# 2_waffling60-DB_matrix.net
KiCad netlist of a schematic drawn in Altium Designer
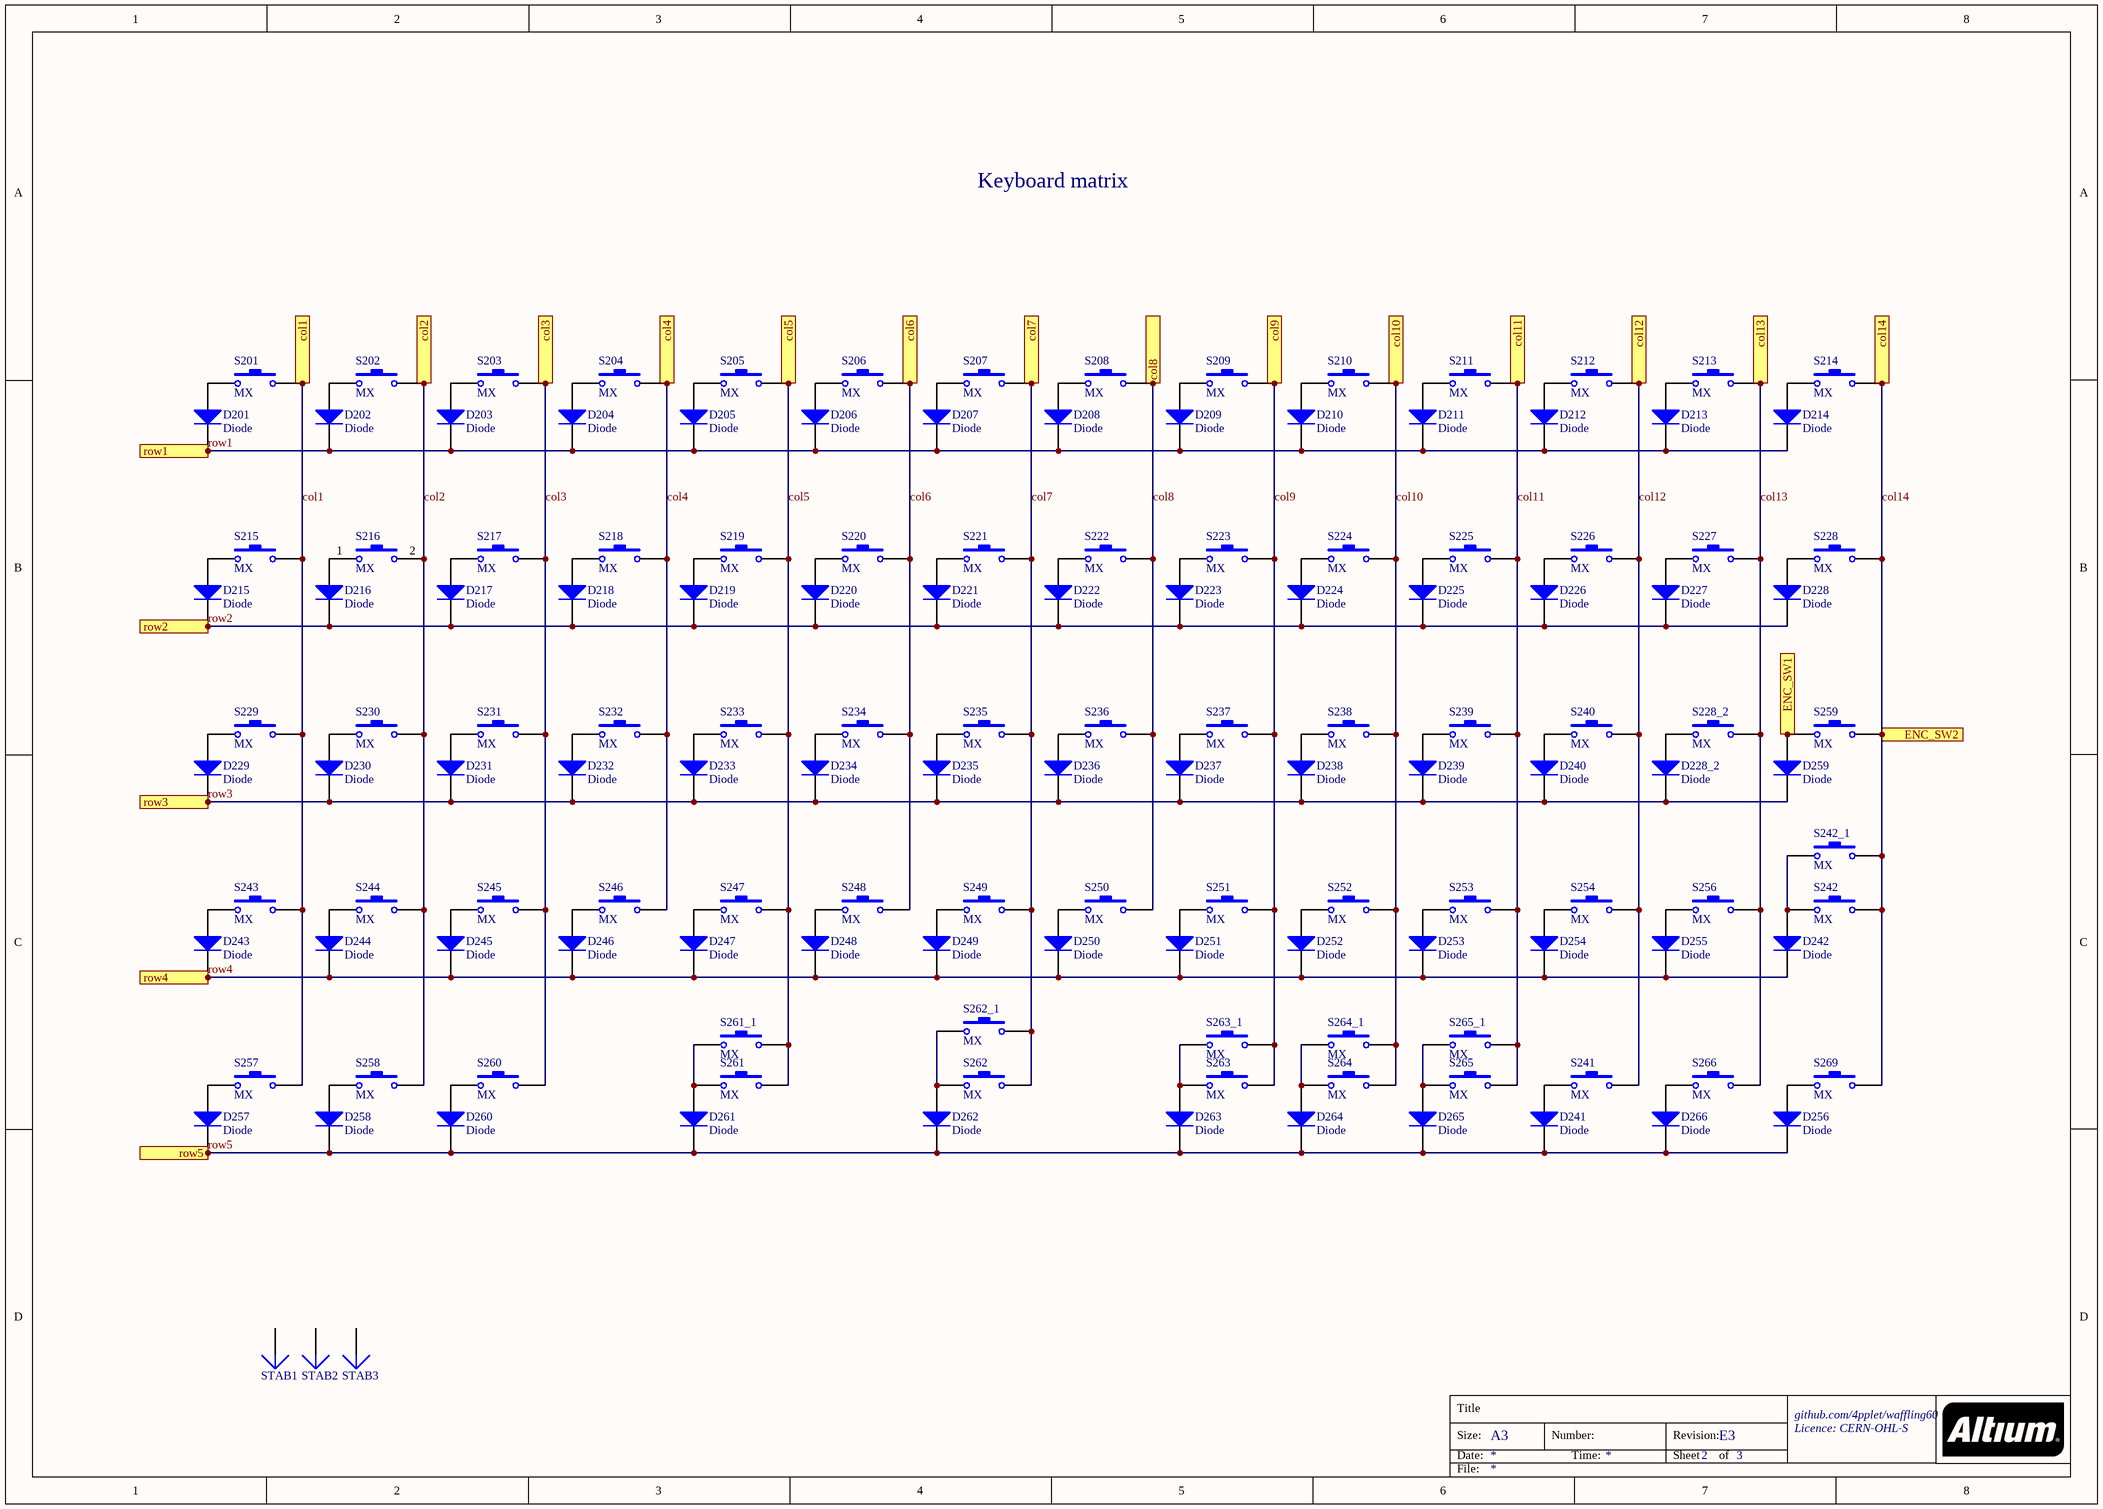
[diagram p0: 2_waffling60-DB_matrix.SchDoc]

(export (version "E")
  (design (tool "Eeschema 10.0.6"))
  (components
    (comp (ref "D201")
      (value "Diode")
      (footprint "SOD-123")
      (description "Default Diode")
      (fields (field (name "LCSC PART #") "C81598") (field (name "MRF.PART") "1N4148W"))
      (libsource (lib "Miscellaneous Devices") (part "Diode"))
    )
    (comp (ref "D202")
      (value "Diode")
      (footprint "SOD-123")
      (description "Default Diode")
      (fields (field (name "LCSC PART #") "C81598") (field (name "MRF.PART") "1N4148W"))
      (libsource (lib "Miscellaneous Devices") (part "Diode"))
    )
    (comp (ref "D203")
      (value "Diode")
      (footprint "SOD-123")
      (description "Default Diode")
      (fields (field (name "LCSC PART #") "C81598") (field (name "MRF.PART") "1N4148W"))
      (libsource (lib "Miscellaneous Devices") (part "Diode"))
    )
    (comp (ref "D204")
      (value "Diode")
      (footprint "SOD-123")
      (description "Default Diode")
      (fields (field (name "LCSC PART #") "C81598") (field (name "MRF.PART") "1N4148W"))
      (libsource (lib "Miscellaneous Devices") (part "Diode"))
    )
    (comp (ref "D205")
      (value "Diode")
      (footprint "SOD-123")
      (description "Default Diode")
      (fields (field (name "LCSC PART #") "C81598") (field (name "MRF.PART") "1N4148W"))
      (libsource (lib "Miscellaneous Devices") (part "Diode"))
    )
    (comp (ref "D206")
      (value "Diode")
      (footprint "SOD-123")
      (description "Default Diode")
      (fields (field (name "LCSC PART #") "C81598") (field (name "MRF.PART") "1N4148W"))
      (libsource (lib "Miscellaneous Devices") (part "Diode"))
    )
    (comp (ref "D207")
      (value "Diode")
      (footprint "SOD-123")
      (description "Default Diode")
      (fields (field (name "LCSC PART #") "C81598") (field (name "MRF.PART") "1N4148W"))
      (libsource (lib "Miscellaneous Devices") (part "Diode"))
    )
    (comp (ref "D208")
      (value "Diode")
      (footprint "SOD-123")
      (description "Default Diode")
      (fields (field (name "LCSC PART #") "C81598") (field (name "MRF.PART") "1N4148W"))
      (libsource (lib "Miscellaneous Devices") (part "Diode"))
    )
    (comp (ref "D209")
      (value "Diode")
      (footprint "SOD-123")
      (description "Default Diode")
      (fields (field (name "LCSC PART #") "C81598") (field (name "MRF.PART") "1N4148W"))
      (libsource (lib "Miscellaneous Devices") (part "Diode"))
    )
    (comp (ref "D210")
      (value "Diode")
      (footprint "SOD-123")
      (description "Default Diode")
      (fields (field (name "LCSC PART #") "C81598") (field (name "MRF.PART") "1N4148W"))
      (libsource (lib "Miscellaneous Devices") (part "Diode"))
    )
    (comp (ref "D211")
      (value "Diode")
      (footprint "SOD-123")
      (description "Default Diode")
      (fields (field (name "LCSC PART #") "C81598") (field (name "MRF.PART") "1N4148W"))
      (libsource (lib "Miscellaneous Devices") (part "Diode"))
    )
    (comp (ref "D212")
      (value "Diode")
      (footprint "SOD-123")
      (description "Default Diode")
      (fields (field (name "LCSC PART #") "C81598") (field (name "MRF.PART") "1N4148W"))
      (libsource (lib "Miscellaneous Devices") (part "Diode"))
    )
    (comp (ref "D213")
      (value "Diode")
      (footprint "SOD-123")
      (description "Default Diode")
      (fields (field (name "LCSC PART #") "C81598") (field (name "MRF.PART") "1N4148W"))
      (libsource (lib "Miscellaneous Devices") (part "Diode"))
    )
    (comp (ref "D214")
      (value "Diode")
      (footprint "SOD-123")
      (description "Default Diode")
      (fields (field (name "LCSC PART #") "C81598") (field (name "MRF.PART") "1N4148W"))
      (libsource (lib "Miscellaneous Devices") (part "Diode"))
    )
    (comp (ref "D215")
      (value "Diode")
      (footprint "SOD-123")
      (description "Default Diode")
      (fields (field (name "LCSC PART #") "C81598") (field (name "MRF.PART") "1N4148W"))
      (libsource (lib "Miscellaneous Devices") (part "Diode"))
    )
    (comp (ref "D216")
      (value "Diode")
      (footprint "SOD-123")
      (description "Default Diode")
      (fields (field (name "LCSC PART #") "C81598") (field (name "MRF.PART") "1N4148W"))
      (libsource (lib "Miscellaneous Devices") (part "Diode"))
    )
    (comp (ref "D217")
      (value "Diode")
      (footprint "SOD-123")
      (description "Default Diode")
      (fields (field (name "LCSC PART #") "C81598") (field (name "MRF.PART") "1N4148W"))
      (libsource (lib "Miscellaneous Devices") (part "Diode"))
    )
    (comp (ref "D218")
      (value "Diode")
      (footprint "SOD-123")
      (description "Default Diode")
      (fields (field (name "LCSC PART #") "C81598") (field (name "MRF.PART") "1N4148W"))
      (libsource (lib "Miscellaneous Devices") (part "Diode"))
    )
    (comp (ref "D219")
      (value "Diode")
      (footprint "SOD-123")
      (description "Default Diode")
      (fields (field (name "LCSC PART #") "C81598") (field (name "MRF.PART") "1N4148W"))
      (libsource (lib "Miscellaneous Devices") (part "Diode"))
    )
    (comp (ref "D220")
      (value "Diode")
      (footprint "SOD-123")
      (description "Default Diode")
      (fields (field (name "LCSC PART #") "C81598") (field (name "MRF.PART") "1N4148W"))
      (libsource (lib "Miscellaneous Devices") (part "Diode"))
    )
    (comp (ref "D221")
      (value "Diode")
      (footprint "SOD-123")
      (description "Default Diode")
      (fields (field (name "LCSC PART #") "C81598") (field (name "MRF.PART") "1N4148W"))
      (libsource (lib "Miscellaneous Devices") (part "Diode"))
    )
    (comp (ref "D222")
      (value "Diode")
      (footprint "SOD-123")
      (description "Default Diode")
      (fields (field (name "LCSC PART #") "C81598") (field (name "MRF.PART") "1N4148W"))
      (libsource (lib "Miscellaneous Devices") (part "Diode"))
    )
    (comp (ref "D223")
      (value "Diode")
      (footprint "SOD-123")
      (description "Default Diode")
      (fields (field (name "LCSC PART #") "C81598") (field (name "MRF.PART") "1N4148W"))
      (libsource (lib "Miscellaneous Devices") (part "Diode"))
    )
    (comp (ref "D224")
      (value "Diode")
      (footprint "SOD-123")
      (description "Default Diode")
      (fields (field (name "LCSC PART #") "C81598") (field (name "MRF.PART") "1N4148W"))
      (libsource (lib "Miscellaneous Devices") (part "Diode"))
    )
    (comp (ref "D225")
      (value "Diode")
      (footprint "SOD-123")
      (description "Default Diode")
      (fields (field (name "LCSC PART #") "C81598") (field (name "MRF.PART") "1N4148W"))
      (libsource (lib "Miscellaneous Devices") (part "Diode"))
    )
    (comp (ref "D226")
      (value "Diode")
      (footprint "SOD-123")
      (description "Default Diode")
      (fields (field (name "LCSC PART #") "C81598") (field (name "MRF.PART") "1N4148W"))
      (libsource (lib "Miscellaneous Devices") (part "Diode"))
    )
    (comp (ref "D227")
      (value "Diode")
      (footprint "SOD-123")
      (description "Default Diode")
      (fields (field (name "LCSC PART #") "C81598") (field (name "MRF.PART") "1N4148W"))
      (libsource (lib "Miscellaneous Devices") (part "Diode"))
    )
    (comp (ref "D228")
      (value "Diode")
      (footprint "SOD-123")
      (description "Default Diode")
      (fields (field (name "LCSC PART #") "C81598") (field (name "MRF.PART") "1N4148W"))
      (libsource (lib "Miscellaneous Devices") (part "Diode"))
    )
    (comp (ref "D228_2")
      (value "Diode")
      (footprint "SOD-123")
      (description "Default Diode")
      (fields (field (name "LCSC PART #") "C81598") (field (name "MRF.PART") "1N4148W"))
      (libsource (lib "Miscellaneous Devices") (part "Diode"))
    )
    (comp (ref "D229")
      (value "Diode")
      (footprint "SOD-123")
      (description "Default Diode")
      (fields (field (name "LCSC PART #") "C81598") (field (name "MRF.PART") "1N4148W"))
      (libsource (lib "Miscellaneous Devices") (part "Diode"))
    )
    (comp (ref "D230")
      (value "Diode")
      (footprint "SOD-123")
      (description "Default Diode")
      (fields (field (name "LCSC PART #") "C81598") (field (name "MRF.PART") "1N4148W"))
      (libsource (lib "Miscellaneous Devices") (part "Diode"))
    )
    (comp (ref "D231")
      (value "Diode")
      (footprint "SOD-123")
      (description "Default Diode")
      (fields (field (name "LCSC PART #") "C81598") (field (name "MRF.PART") "1N4148W"))
      (libsource (lib "Miscellaneous Devices") (part "Diode"))
    )
    (comp (ref "D232")
      (value "Diode")
      (footprint "SOD-123")
      (description "Default Diode")
      (fields (field (name "LCSC PART #") "C81598") (field (name "MRF.PART") "1N4148W"))
      (libsource (lib "Miscellaneous Devices") (part "Diode"))
    )
    (comp (ref "D233")
      (value "Diode")
      (footprint "SOD-123")
      (description "Default Diode")
      (fields (field (name "LCSC PART #") "C81598") (field (name "MRF.PART") "1N4148W"))
      (libsource (lib "Miscellaneous Devices") (part "Diode"))
    )
    (comp (ref "D234")
      (value "Diode")
      (footprint "SOD-123")
      (description "Default Diode")
      (fields (field (name "LCSC PART #") "C81598") (field (name "MRF.PART") "1N4148W"))
      (libsource (lib "Miscellaneous Devices") (part "Diode"))
    )
    (comp (ref "D235")
      (value "Diode")
      (footprint "SOD-123")
      (description "Default Diode")
      (fields (field (name "LCSC PART #") "C81598") (field (name "MRF.PART") "1N4148W"))
      (libsource (lib "Miscellaneous Devices") (part "Diode"))
    )
    (comp (ref "D236")
      (value "Diode")
      (footprint "SOD-123")
      (description "Default Diode")
      (fields (field (name "LCSC PART #") "C81598") (field (name "MRF.PART") "1N4148W"))
      (libsource (lib "Miscellaneous Devices") (part "Diode"))
    )
    (comp (ref "D237")
      (value "Diode")
      (footprint "SOD-123")
      (description "Default Diode")
      (fields (field (name "LCSC PART #") "C81598") (field (name "MRF.PART") "1N4148W"))
      (libsource (lib "Miscellaneous Devices") (part "Diode"))
    )
    (comp (ref "D238")
      (value "Diode")
      (footprint "SOD-123")
      (description "Default Diode")
      (fields (field (name "LCSC PART #") "C81598") (field (name "MRF.PART") "1N4148W"))
      (libsource (lib "Miscellaneous Devices") (part "Diode"))
    )
    (comp (ref "D239")
      (value "Diode")
      (footprint "SOD-123")
      (description "Default Diode")
      (fields (field (name "LCSC PART #") "C81598") (field (name "MRF.PART") "1N4148W"))
      (libsource (lib "Miscellaneous Devices") (part "Diode"))
    )
    (comp (ref "D240")
      (value "Diode")
      (footprint "SOD-123")
      (description "Default Diode")
      (fields (field (name "LCSC PART #") "C81598") (field (name "MRF.PART") "1N4148W"))
      (libsource (lib "Miscellaneous Devices") (part "Diode"))
    )
    (comp (ref "D241")
      (value "Diode")
      (footprint "SOD-123")
      (description "Default Diode")
      (fields (field (name "LCSC PART #") "C81598") (field (name "MRF.PART") "1N4148W"))
      (libsource (lib "Miscellaneous Devices") (part "Diode"))
    )
    (comp (ref "D242")
      (value "Diode")
      (footprint "SOD-123")
      (description "Default Diode")
      (fields (field (name "LCSC PART #") "C81598") (field (name "MRF.PART") "1N4148W"))
      (libsource (lib "Miscellaneous Devices") (part "Diode"))
    )
    (comp (ref "D243")
      (value "Diode")
      (footprint "SOD-123")
      (description "Default Diode")
      (fields (field (name "LCSC PART #") "C81598") (field (name "MRF.PART") "1N4148W"))
      (libsource (lib "Miscellaneous Devices") (part "Diode"))
    )
    (comp (ref "D244")
      (value "Diode")
      (footprint "SOD-123")
      (description "Default Diode")
      (fields (field (name "LCSC PART #") "C81598") (field (name "MRF.PART") "1N4148W"))
      (libsource (lib "Miscellaneous Devices") (part "Diode"))
    )
    (comp (ref "D245")
      (value "Diode")
      (footprint "SOD-123")
      (description "Default Diode")
      (fields (field (name "LCSC PART #") "C81598") (field (name "MRF.PART") "1N4148W"))
      (libsource (lib "Miscellaneous Devices") (part "Diode"))
    )
    (comp (ref "D246")
      (value "Diode")
      (footprint "SOD-123")
      (description "Default Diode")
      (fields (field (name "LCSC PART #") "C81598") (field (name "MRF.PART") "1N4148W"))
      (libsource (lib "Miscellaneous Devices") (part "Diode"))
    )
    (comp (ref "D247")
      (value "Diode")
      (footprint "SOD-123")
      (description "Default Diode")
      (fields (field (name "LCSC PART #") "C81598") (field (name "MRF.PART") "1N4148W"))
      (libsource (lib "Miscellaneous Devices") (part "Diode"))
    )
    (comp (ref "D248")
      (value "Diode")
      (footprint "SOD-123")
      (description "Default Diode")
      (fields (field (name "LCSC PART #") "C81598") (field (name "MRF.PART") "1N4148W"))
      (libsource (lib "Miscellaneous Devices") (part "Diode"))
    )
    (comp (ref "D249")
      (value "Diode")
      (footprint "SOD-123")
      (description "Default Diode")
      (fields (field (name "LCSC PART #") "C81598") (field (name "MRF.PART") "1N4148W"))
      (libsource (lib "Miscellaneous Devices") (part "Diode"))
    )
    (comp (ref "D250")
      (value "Diode")
      (footprint "SOD-123")
      (description "Default Diode")
      (fields (field (name "LCSC PART #") "C81598") (field (name "MRF.PART") "1N4148W"))
      (libsource (lib "Miscellaneous Devices") (part "Diode"))
    )
    (comp (ref "D251")
      (value "Diode")
      (footprint "SOD-123")
      (description "Default Diode")
      (fields (field (name "LCSC PART #") "C81598") (field (name "MRF.PART") "1N4148W"))
      (libsource (lib "Miscellaneous Devices") (part "Diode"))
    )
    (comp (ref "D252")
      (value "Diode")
      (footprint "SOD-123")
      (description "Default Diode")
      (fields (field (name "LCSC PART #") "C81598") (field (name "MRF.PART") "1N4148W"))
      (libsource (lib "Miscellaneous Devices") (part "Diode"))
    )
    (comp (ref "D253")
      (value "Diode")
      (footprint "SOD-123")
      (description "Default Diode")
      (fields (field (name "LCSC PART #") "C81598") (field (name "MRF.PART") "1N4148W"))
      (libsource (lib "Miscellaneous Devices") (part "Diode"))
    )
    (comp (ref "D254")
      (value "Diode")
      (footprint "SOD-123")
      (description "Default Diode")
      (fields (field (name "LCSC PART #") "C81598") (field (name "MRF.PART") "1N4148W"))
      (libsource (lib "Miscellaneous Devices") (part "Diode"))
    )
    (comp (ref "D255")
      (value "Diode")
      (footprint "SOD-123")
      (description "Default Diode")
      (fields (field (name "LCSC PART #") "C81598") (field (name "MRF.PART") "1N4148W"))
      (libsource (lib "Miscellaneous Devices") (part "Diode"))
    )
    (comp (ref "D256")
      (value "Diode")
      (footprint "SOD-123")
      (description "Default Diode")
      (fields (field (name "LCSC PART #") "C81598") (field (name "MRF.PART") "1N4148W"))
      (libsource (lib "Miscellaneous Devices") (part "Diode"))
    )
    (comp (ref "D257")
      (value "Diode")
      (footprint "SOD-123")
      (description "Default Diode")
      (fields (field (name "LCSC PART #") "C81598") (field (name "MRF.PART") "1N4148W"))
      (libsource (lib "Miscellaneous Devices") (part "Diode"))
    )
    (comp (ref "D258")
      (value "Diode")
      (footprint "SOD-123")
      (description "Default Diode")
      (fields (field (name "LCSC PART #") "C81598") (field (name "MRF.PART") "1N4148W"))
      (libsource (lib "Miscellaneous Devices") (part "Diode"))
    )
    (comp (ref "D259")
      (value "Diode")
      (footprint "SOD-123")
      (description "Default Diode")
      (fields (field (name "LCSC PART #") "C81598") (field (name "MRF.PART") "1N4148W"))
      (libsource (lib "Miscellaneous Devices") (part "Diode"))
    )
    (comp (ref "D260")
      (value "Diode")
      (footprint "SOD-123")
      (description "Default Diode")
      (fields (field (name "LCSC PART #") "C81598") (field (name "MRF.PART") "1N4148W"))
      (libsource (lib "Miscellaneous Devices") (part "Diode"))
    )
    (comp (ref "D261")
      (value "Diode")
      (footprint "SOD-123")
      (description "Default Diode")
      (fields (field (name "LCSC PART #") "C81598") (field (name "MRF.PART") "1N4148W"))
      (libsource (lib "Miscellaneous Devices") (part "Diode"))
    )
    (comp (ref "D262")
      (value "Diode")
      (footprint "SOD-123")
      (description "Default Diode")
      (fields (field (name "LCSC PART #") "C81598") (field (name "MRF.PART") "1N4148W"))
      (libsource (lib "Miscellaneous Devices") (part "Diode"))
    )
    (comp (ref "D263")
      (value "Diode")
      (footprint "SOD-123")
      (description "Default Diode")
      (fields (field (name "LCSC PART #") "C81598") (field (name "MRF.PART") "1N4148W"))
      (libsource (lib "Miscellaneous Devices") (part "Diode"))
    )
    (comp (ref "D264")
      (value "Diode")
      (footprint "SOD-123")
      (description "Default Diode")
      (fields (field (name "LCSC PART #") "C81598") (field (name "MRF.PART") "1N4148W"))
      (libsource (lib "Miscellaneous Devices") (part "Diode"))
    )
    (comp (ref "D265")
      (value "Diode")
      (footprint "SOD-123")
      (description "Default Diode")
      (fields (field (name "LCSC PART #") "C81598") (field (name "MRF.PART") "1N4148W"))
      (libsource (lib "Miscellaneous Devices") (part "Diode"))
    )
    (comp (ref "D266")
      (value "Diode")
      (footprint "SOD-123")
      (description "Default Diode")
      (fields (field (name "LCSC PART #") "C81598") (field (name "MRF.PART") "1N4148W"))
      (libsource (lib "Miscellaneous Devices") (part "Diode"))
    )
    (comp (ref "S201")
      (value "MX")
      (footprint "MX-switch - switched pol")
      (description "Switch")
      (libsource (lib "Miscellaneous Devices") (part "SW-PB"))
    )
    (comp (ref "S202")
      (value "MX")
      (footprint "MX-switch - switched pol")
      (description "Switch")
      (libsource (lib "Miscellaneous Devices") (part "SW-PB"))
    )
    (comp (ref "S203")
      (value "MX")
      (footprint "MX-switch - switched pol")
      (description "Switch")
      (libsource (lib "Miscellaneous Devices") (part "SW-PB"))
    )
    (comp (ref "S204")
      (value "MX")
      (footprint "MX-switch - switched pol")
      (description "Switch")
      (libsource (lib "Miscellaneous Devices") (part "SW-PB"))
    )
    (comp (ref "S205")
      (value "MX")
      (footprint "MX-switch - switched pol")
      (description "Switch")
      (libsource (lib "Miscellaneous Devices") (part "SW-PB"))
    )
    (comp (ref "S206")
      (value "MX")
      (footprint "MX-switch - switched pol")
      (description "Switch")
      (libsource (lib "Miscellaneous Devices") (part "SW-PB"))
    )
    (comp (ref "S207")
      (value "MX")
      (footprint "MX-switch - switched pol")
      (description "Switch")
      (libsource (lib "Miscellaneous Devices") (part "SW-PB"))
    )
    (comp (ref "S208")
      (value "MX")
      (footprint "MX-switch - switched pol")
      (description "Switch")
      (libsource (lib "Miscellaneous Devices") (part "SW-PB"))
    )
    (comp (ref "S209")
      (value "MX")
      (footprint "MX-switch - switched pol")
      (description "Switch")
      (libsource (lib "Miscellaneous Devices") (part "SW-PB"))
    )
    (comp (ref "S210")
      (value "MX")
      (footprint "MX-switch - switched pol")
      (description "Switch")
      (libsource (lib "Miscellaneous Devices") (part "SW-PB"))
    )
    (comp (ref "S211")
      (value "MX")
      (footprint "MX-switch - switched pol")
      (description "Switch")
      (libsource (lib "Miscellaneous Devices") (part "SW-PB"))
    )
    (comp (ref "S212")
      (value "MX")
      (footprint "MX-switch - switched pol")
      (description "Switch")
      (libsource (lib "Miscellaneous Devices") (part "SW-PB"))
    )
    (comp (ref "S213")
      (value "MX")
      (footprint "MX-switch - switched pol")
      (description "Switch")
      (libsource (lib "Miscellaneous Devices") (part "SW-PB"))
    )
    (comp (ref "S214")
      (value "MX")
      (footprint "MX-switch")
      (description "Switch")
      (libsource (lib "Miscellaneous Devices") (part "SW-PB"))
    )
    (comp (ref "S215")
      (value "MX")
      (footprint "MX-switch - switched pol")
      (description "TAB")
      (libsource (lib "Miscellaneous Devices") (part "SW-PB"))
    )
    (comp (ref "S216")
      (value "MX")
      (footprint "MX-switch")
      (description "Switch")
      (libsource (lib "") (part "SW-PB_1"))
    )
    (comp (ref "S217")
      (value "MX")
      (footprint "MX-switch - switched pol")
      (description "Switch")
      (libsource (lib "Miscellaneous Devices") (part "SW-PB"))
    )
    (comp (ref "S218")
      (value "MX")
      (footprint "MX-switch - switched pol")
      (description "Switch")
      (libsource (lib "Miscellaneous Devices") (part "SW-PB"))
    )
    (comp (ref "S219")
      (value "MX")
      (footprint "MX-switch - switched pol")
      (description "Switch")
      (libsource (lib "Miscellaneous Devices") (part "SW-PB"))
    )
    (comp (ref "S220")
      (value "MX")
      (footprint "MX-switch")
      (description "Switch")
      (libsource (lib "Miscellaneous Devices") (part "SW-PB"))
    )
    (comp (ref "S221")
      (value "MX")
      (footprint "MX-switch - switched pol")
      (description "Switch")
      (libsource (lib "Miscellaneous Devices") (part "SW-PB"))
    )
    (comp (ref "S222")
      (value "MX")
      (footprint "MX-switch - switched pol")
      (description "Switch")
      (libsource (lib "Miscellaneous Devices") (part "SW-PB"))
    )
    (comp (ref "S223")
      (value "MX")
      (footprint "MX-switch - switched pol")
      (description "Switch")
      (libsource (lib "Miscellaneous Devices") (part "SW-PB"))
    )
    (comp (ref "S224")
      (value "MX")
      (footprint "MX-switch - switched pol")
      (description "Switch")
      (libsource (lib "Miscellaneous Devices") (part "SW-PB"))
    )
    (comp (ref "S225")
      (value "MX")
      (footprint "MX-switch - switched pol")
      (description "Switch")
      (libsource (lib "Miscellaneous Devices") (part "SW-PB"))
    )
    (comp (ref "S226")
      (value "MX")
      (footprint "MX-switch")
      (description "Switch")
      (libsource (lib "Miscellaneous Devices") (part "SW-PB"))
    )
    (comp (ref "S227")
      (value "MX")
      (footprint "MX-switch")
      (description "Switch")
      (libsource (lib "Miscellaneous Devices") (part "SW-PB"))
    )
    (comp (ref "S228")
      (value "MX")
      (footprint "MX-switch - 1.5U")
      (description "Switch")
      (libsource (lib "Miscellaneous Devices") (part "SW-PB"))
    )
    (comp (ref "S228_2")
      (value "MX")
      (footprint "MX-switch")
      (description "Switch")
      (libsource (lib "Miscellaneous Devices") (part "SW-PB"))
    )
    (comp (ref "S229")
      (value "MX")
      (footprint "MX-switch - CAPS")
      (description "Switch")
      (libsource (lib "Miscellaneous Devices") (part "SW-PB"))
    )
    (comp (ref "S230")
      (value "MX")
      (footprint "MX-switch")
      (description "Switch")
      (libsource (lib "Miscellaneous Devices") (part "SW-PB"))
    )
    (comp (ref "S231")
      (value "MX")
      (footprint "MX-switch - switched pol")
      (description "Switch")
      (libsource (lib "Miscellaneous Devices") (part "SW-PB"))
    )
    (comp (ref "S232")
      (value "MX")
      (footprint "MX-switch - switched pol")
      (description "Switch")
      (libsource (lib "Miscellaneous Devices") (part "SW-PB"))
    )
    (comp (ref "S233")
      (value "MX")
      (footprint "MX-switch - switched pol")
      (description "Switch")
      (libsource (lib "Miscellaneous Devices") (part "SW-PB"))
    )
    (comp (ref "S234")
      (value "MX")
      (footprint "MX-switch - switched pol")
      (description "Switch")
      (libsource (lib "Miscellaneous Devices") (part "SW-PB"))
    )
    (comp (ref "S235")
      (value "MX")
      (footprint "MX-switch - switched pol")
      (description "Switch")
      (libsource (lib "Miscellaneous Devices") (part "SW-PB"))
    )
    (comp (ref "S236")
      (value "MX")
      (footprint "MX-switch - switched pol")
      (description "Switch")
      (libsource (lib "Miscellaneous Devices") (part "SW-PB"))
    )
    (comp (ref "S237")
      (value "MX")
      (footprint "MX-switch - switched pol")
      (description "Switch")
      (libsource (lib "Miscellaneous Devices") (part "SW-PB"))
    )
    (comp (ref "S238")
      (value "MX")
      (footprint "MX-switch - switched pol")
      (description "Switch")
      (libsource (lib "Miscellaneous Devices") (part "SW-PB"))
    )
    (comp (ref "S239")
      (value "MX")
      (footprint "MX-switch - switched pol")
      (description "Switch")
      (libsource (lib "Miscellaneous Devices") (part "SW-PB"))
    )
    (comp (ref "S240")
      (value "MX")
      (footprint "MX-switch - switched pol")
      (description "Switch")
      (libsource (lib "Miscellaneous Devices") (part "SW-PB"))
    )
    (comp (ref "S241")
      (value "MX")
      (footprint "MX-switch - 1u MOD-R")
      (description "Switch")
      (libsource (lib "Miscellaneous Devices") (part "SW-PB"))
    )
    (comp (ref "S242")
      (value "MX")
      (footprint "MX-switch - switched pol")
      (description "Switch")
      (libsource (lib "Miscellaneous Devices") (part "SW-PB"))
    )
    (comp (ref "S242_1")
      (value "MX")
      (footprint "MX-switch - switched pol")
      (description "Switch")
      (libsource (lib "Miscellaneous Devices") (part "SW-PB"))
    )
    (comp (ref "S243")
      (value "MX")
      (footprint "MX-switch - Left shift")
      (description "Switch")
      (libsource (lib "Miscellaneous Devices") (part "SW-PB"))
    )
    (comp (ref "S244")
      (value "MX")
      (footprint "MX-switch")
      (description "Switch")
      (libsource (lib "Miscellaneous Devices") (part "SW-PB"))
    )
    (comp (ref "S245")
      (value "MX")
      (footprint "MX-switch - switched pol")
      (description "Switch")
      (libsource (lib "Miscellaneous Devices") (part "SW-PB"))
    )
    (comp (ref "S246")
      (value "MX")
      (footprint "MX-switch - switched pol")
      (description "Switch")
      (libsource (lib "Miscellaneous Devices") (part "SW-PB"))
    )
    (comp (ref "S247")
      (value "MX")
      (footprint "MX-switch - switched pol")
      (description "Switch")
      (libsource (lib "Miscellaneous Devices") (part "SW-PB"))
    )
    (comp (ref "S248")
      (value "MX")
      (footprint "MX-switch - switched pol")
      (description "Switch")
      (libsource (lib "Miscellaneous Devices") (part "SW-PB"))
    )
    (comp (ref "S249")
      (value "MX")
      (footprint "MX-switch - switched pol")
      (description "Switch")
      (libsource (lib "Miscellaneous Devices") (part "SW-PB"))
    )
    (comp (ref "S250")
      (value "MX")
      (footprint "MX-switch - switched pol")
      (description "Switch")
      (libsource (lib "Miscellaneous Devices") (part "SW-PB"))
    )
    (comp (ref "S251")
      (value "MX")
      (footprint "MX-switch - switched pol")
      (description "Switch")
      (libsource (lib "Miscellaneous Devices") (part "SW-PB"))
    )
    (comp (ref "S252")
      (value "MX")
      (footprint "MX-switch - switched pol")
      (description "Switch")
      (libsource (lib "Miscellaneous Devices") (part "SW-PB"))
    )
    (comp (ref "S253")
      (value "MX")
      (footprint "MX-switch - switched pol")
      (description "Switch")
      (libsource (lib "Miscellaneous Devices") (part "SW-PB"))
    )
    (comp (ref "S254")
      (value "MX")
      (footprint "MX-switch - switched pol")
      (description "Switch")
      (libsource (lib "Miscellaneous Devices") (part "SW-PB"))
    )
    (comp (ref "S256")
      (value "MX")
      (footprint "MX-switch - right shift")
      (description "Switch")
      (libsource (lib "Miscellaneous Devices") (part "SW-PB"))
    )
    (comp (ref "S257")
      (value "MX")
      (footprint "MX-switch - 1.5u MOD-L")
      (description "Switch")
      (libsource (lib "Miscellaneous Devices") (part "SW-PB"))
    )
    (comp (ref "S258")
      (value "MX")
      (footprint "MX-switch - 1u MOD-L")
      (description "Switch")
      (libsource (lib "Miscellaneous Devices") (part "SW-PB"))
    )
    (comp (ref "S259")
      (value "MX")
      (footprint "MX-switch - backspace")
      (description "Switch")
      (libsource (lib "Miscellaneous Devices") (part "SW-PB"))
    )
    (comp (ref "S260")
      (value "MX")
      (footprint "MX-switch - 1.5u MOD-L")
      (description "Switch")
      (libsource (lib "Miscellaneous Devices") (part "SW-PB"))
    )
    (comp (ref "S261")
      (value "MX")
      (footprint "MX-SWITCH - L SPLIT SPACE_V2")
      (description "Switch")
      (libsource (lib "Miscellaneous Devices") (part "SW-PB"))
    )
    (comp (ref "S261_1")
      (value "MX")
      (footprint "MX-switch - 3U - rotated stab")
      (description "Switch")
      (libsource (lib "Miscellaneous Devices") (part "SW-PB"))
    )
    (comp (ref "S262")
      (value "MX")
      (footprint "MX-switch - Space_V3")
      (description "Switch")
      (libsource (lib "Miscellaneous Devices") (part "SW-PB"))
    )
    (comp (ref "S262_1")
      (value "MX")
      (footprint "MX-switch - switched pol")
      (description "Switch")
      (libsource (lib "Miscellaneous Devices") (part "SW-PB"))
    )
    (comp (ref "S263")
      (value "MX")
      (footprint "MX-SWITCH - R SPLIT SPACE_V2")
      (description "Switch")
      (libsource (lib "Miscellaneous Devices") (part "SW-PB"))
    )
    (comp (ref "S263_1")
      (value "MX")
      (footprint "MX-switch - 3U - rotated stab")
      (description "Switch")
      (libsource (lib "Miscellaneous Devices") (part "SW-PB"))
    )
    (comp (ref "S264")
      (value "MX")
      (footprint "MX-switch")
      (description "Switch")
      (libsource (lib "Miscellaneous Devices") (part "SW-PB"))
    )
    (comp (ref "S264_1")
      (value "MX")
      (footprint "MX-switch - switched pol")
      (description "Switch")
      (libsource (lib "Miscellaneous Devices") (part "SW-PB"))
    )
    (comp (ref "S265")
      (value "MX")
      (footprint "MX-switch - 1.5u MOD-R")
      (description "Switch")
      (libsource (lib "Miscellaneous Devices") (part "SW-PB"))
    )
    (comp (ref "S265_1")
      (value "MX")
      (footprint "MX-switch - switched pol")
      (description "Switch")
      (libsource (lib "Miscellaneous Devices") (part "SW-PB"))
    )
    (comp (ref "S266")
      (value "MX")
      (footprint "MX-switch - 1.5u MOD-R")
      (description "Switch")
      (libsource (lib "Miscellaneous Devices") (part "SW-PB"))
    )
    (comp (ref "S269")
      (value "MX")
      (footprint "MX-switch")
      (description "Switch")
      (libsource (lib "Miscellaneous Devices") (part "SW-PB"))
    )
    (comp (ref "STAB1")
      (value "Plug")
      (footprint "Stab 10U")
      (libsource (lib "Miscellaneous Connectors") (part "Plug"))
    )
    (comp (ref "STAB2")
      (value "Plug")
      (footprint "Stab 2u")
      (libsource (lib "Miscellaneous Connectors") (part "Plug"))
    )
    (comp (ref "STAB3")
      (value "Plug")
      (footprint "Stab 2u")
      (libsource (lib "Miscellaneous Connectors") (part "Plug"))
    )
  )
  (nets
    (net (code "1") (name "/ENC_SW1") (class "Default")
      (node (ref "D259") (pin "1") (pinfunction "A_1") (pintype "passive"))
      (node (ref "S259") (pin "1") (pinfunction "1_1") (pintype "passive"))
    )
    (net (code "2") (name "/col1") (class "Default")
      (node (ref "S201") (pin "2") (pinfunction "2_2") (pintype "passive"))
      (node (ref "S215") (pin "2") (pinfunction "2_2") (pintype "passive"))
      (node (ref "S229") (pin "1") (pinfunction "1_1") (pintype "passive"))
      (node (ref "S243") (pin "2") (pinfunction "2_2") (pintype "passive"))
      (node (ref "S257") (pin "1") (pinfunction "1_1") (pintype "passive"))
    )
    (net (code "3") (name "/col2") (class "Default")
      (node (ref "S202") (pin "2") (pinfunction "2_2") (pintype "passive"))
      (node (ref "S216") (pin "2") (pinfunction "2_2") (pintype "passive"))
      (node (ref "S230") (pin "2") (pinfunction "2_2") (pintype "passive"))
      (node (ref "S244") (pin "1") (pinfunction "1_1") (pintype "passive"))
      (node (ref "S258") (pin "2") (pinfunction "2_2") (pintype "passive"))
    )
    (net (code "4") (name "/col3") (class "Default")
      (node (ref "S203") (pin "2") (pinfunction "2_2") (pintype "passive"))
      (node (ref "S217") (pin "2") (pinfunction "2_2") (pintype "passive"))
      (node (ref "S231") (pin "2") (pinfunction "2_2") (pintype "passive"))
      (node (ref "S245") (pin "2") (pinfunction "2_2") (pintype "passive"))
      (node (ref "S260") (pin "2") (pinfunction "2_2") (pintype "passive"))
    )
    (net (code "5") (name "/col4") (class "Default")
      (node (ref "S204") (pin "2") (pinfunction "2_2") (pintype "passive"))
      (node (ref "S218") (pin "2") (pinfunction "2_2") (pintype "passive"))
      (node (ref "S232") (pin "2") (pinfunction "2_2") (pintype "passive"))
      (node (ref "S246") (pin "2") (pinfunction "2_2") (pintype "passive"))
    )
    (net (code "6") (name "/col5") (class "Default")
      (node (ref "S205") (pin "2") (pinfunction "2_2") (pintype "passive"))
      (node (ref "S219") (pin "2") (pinfunction "2_2") (pintype "passive"))
      (node (ref "S233") (pin "2") (pinfunction "2_2") (pintype "passive"))
      (node (ref "S247") (pin "2") (pinfunction "2_2") (pintype "passive"))
      (node (ref "S261") (pin "2") (pinfunction "2_2") (pintype "passive"))
      (node (ref "S261_1") (pin "2") (pinfunction "2_2") (pintype "passive"))
    )
    (net (code "7") (name "/col6") (class "Default")
      (node (ref "S206") (pin "2") (pinfunction "2_2") (pintype "passive"))
      (node (ref "S220") (pin "2") (pinfunction "2_2") (pintype "passive"))
      (node (ref "S234") (pin "2") (pinfunction "2_2") (pintype "passive"))
      (node (ref "S248") (pin "2") (pinfunction "2_2") (pintype "passive"))
    )
    (net (code "8") (name "/col7") (class "Default")
      (node (ref "S207") (pin "2") (pinfunction "2_2") (pintype "passive"))
      (node (ref "S221") (pin "2") (pinfunction "2_2") (pintype "passive"))
      (node (ref "S235") (pin "2") (pinfunction "2_2") (pintype "passive"))
      (node (ref "S249") (pin "2") (pinfunction "2_2") (pintype "passive"))
      (node (ref "S262") (pin "1") (pinfunction "1_1") (pintype "passive"))
      (node (ref "S262_1") (pin "1") (pinfunction "1_1") (pintype "passive"))
    )
    (net (code "9") (name "/col8") (class "Default")
      (node (ref "S208") (pin "2") (pinfunction "2_2") (pintype "passive"))
      (node (ref "S222") (pin "2") (pinfunction "2_2") (pintype "passive"))
      (node (ref "S236") (pin "2") (pinfunction "2_2") (pintype "passive"))
      (node (ref "S250") (pin "2") (pinfunction "2_2") (pintype "passive"))
    )
    (net (code "10") (name "/col9") (class "Default")
      (node (ref "S209") (pin "2") (pinfunction "2_2") (pintype "passive"))
      (node (ref "S223") (pin "2") (pinfunction "2_2") (pintype "passive"))
      (node (ref "S237") (pin "2") (pinfunction "2_2") (pintype "passive"))
      (node (ref "S251") (pin "2") (pinfunction "2_2") (pintype "passive"))
      (node (ref "S263") (pin "1") (pinfunction "1_1") (pintype "passive"))
      (node (ref "S263_1") (pin "1") (pinfunction "1_1") (pintype "passive"))
    )
    (net (code "11") (name "/col10") (class "Default")
      (node (ref "S210") (pin "2") (pinfunction "2_2") (pintype "passive"))
      (node (ref "S224") (pin "2") (pinfunction "2_2") (pintype "passive"))
      (node (ref "S238") (pin "2") (pinfunction "2_2") (pintype "passive"))
      (node (ref "S252") (pin "2") (pinfunction "2_2") (pintype "passive"))
      (node (ref "S264") (pin "2") (pinfunction "2_2") (pintype "passive"))
      (node (ref "S264_1") (pin "1") (pinfunction "1_1") (pintype "passive"))
    )
    (net (code "12") (name "/col11") (class "Default")
      (node (ref "S211") (pin "2") (pinfunction "2_2") (pintype "passive"))
      (node (ref "S225") (pin "2") (pinfunction "2_2") (pintype "passive"))
      (node (ref "S239") (pin "2") (pinfunction "2_2") (pintype "passive"))
      (node (ref "S253") (pin "2") (pinfunction "2_2") (pintype "passive"))
      (node (ref "S265") (pin "1") (pinfunction "1_1") (pintype "passive"))
      (node (ref "S265_1") (pin "2") (pinfunction "2_2") (pintype "passive"))
    )
    (net (code "13") (name "/col12") (class "Default")
      (node (ref "S212") (pin "2") (pinfunction "2_2") (pintype "passive"))
      (node (ref "S226") (pin "2") (pinfunction "2_2") (pintype "passive"))
      (node (ref "S240") (pin "2") (pinfunction "2_2") (pintype "passive"))
      (node (ref "S241") (pin "1") (pinfunction "1_1") (pintype "passive"))
      (node (ref "S254") (pin "2") (pinfunction "2_2") (pintype "passive"))
    )
    (net (code "14") (name "/col13") (class "Default")
      (node (ref "S213") (pin "2") (pinfunction "2_2") (pintype "passive"))
      (node (ref "S227") (pin "2") (pinfunction "2_2") (pintype "passive"))
      (node (ref "S228_2") (pin "2") (pinfunction "2_2") (pintype "passive"))
      (node (ref "S256") (pin "2") (pinfunction "2_2") (pintype "passive"))
      (node (ref "S266") (pin "2") (pinfunction "2_2") (pintype "passive"))
    )
    (net (code "15") (name "/col14") (class "Default")
      (node (ref "S214") (pin "2") (pinfunction "2_2") (pintype "passive"))
      (node (ref "S228") (pin "2") (pinfunction "2_2") (pintype "passive"))
      (node (ref "S242") (pin "2") (pinfunction "2_2") (pintype "passive"))
      (node (ref "S242_1") (pin "2") (pinfunction "2_2") (pintype "passive"))
      (node (ref "S259") (pin "2") (pinfunction "2_2") (pintype "passive"))
      (node (ref "S269") (pin "2") (pinfunction "2_2") (pintype "passive"))
    )
    (net (code "16") (name "/row1") (class "Default")
      (node (ref "D201") (pin "2") (pinfunction "K_2") (pintype "passive"))
      (node (ref "D202") (pin "2") (pinfunction "K_2") (pintype "passive"))
      (node (ref "D203") (pin "2") (pinfunction "K_2") (pintype "passive"))
      (node (ref "D204") (pin "2") (pinfunction "K_2") (pintype "passive"))
      (node (ref "D205") (pin "2") (pinfunction "K_2") (pintype "passive"))
      (node (ref "D206") (pin "2") (pinfunction "K_2") (pintype "passive"))
      (node (ref "D207") (pin "2") (pinfunction "K_2") (pintype "passive"))
      (node (ref "D208") (pin "2") (pinfunction "K_2") (pintype "passive"))
      (node (ref "D209") (pin "2") (pinfunction "K_2") (pintype "passive"))
      (node (ref "D210") (pin "2") (pinfunction "K_2") (pintype "passive"))
      (node (ref "D211") (pin "2") (pinfunction "K_2") (pintype "passive"))
      (node (ref "D212") (pin "2") (pinfunction "K_2") (pintype "passive"))
      (node (ref "D213") (pin "2") (pinfunction "K_2") (pintype "passive"))
      (node (ref "D214") (pin "2") (pinfunction "K_2") (pintype "passive"))
    )
    (net (code "17") (name "/row2") (class "Default")
      (node (ref "D215") (pin "2") (pinfunction "K_2") (pintype "passive"))
      (node (ref "D216") (pin "2") (pinfunction "K_2") (pintype "passive"))
      (node (ref "D217") (pin "2") (pinfunction "K_2") (pintype "passive"))
      (node (ref "D218") (pin "2") (pinfunction "K_2") (pintype "passive"))
      (node (ref "D219") (pin "2") (pinfunction "K_2") (pintype "passive"))
      (node (ref "D220") (pin "2") (pinfunction "K_2") (pintype "passive"))
      (node (ref "D221") (pin "2") (pinfunction "K_2") (pintype "passive"))
      (node (ref "D222") (pin "2") (pinfunction "K_2") (pintype "passive"))
      (node (ref "D223") (pin "2") (pinfunction "K_2") (pintype "passive"))
      (node (ref "D224") (pin "2") (pinfunction "K_2") (pintype "passive"))
      (node (ref "D225") (pin "2") (pinfunction "K_2") (pintype "passive"))
      (node (ref "D226") (pin "2") (pinfunction "K_2") (pintype "passive"))
      (node (ref "D227") (pin "2") (pinfunction "K_2") (pintype "passive"))
      (node (ref "D228") (pin "2") (pinfunction "K_2") (pintype "passive"))
    )
    (net (code "18") (name "/row3") (class "Default")
      (node (ref "D228_2") (pin "2") (pinfunction "K_2") (pintype "passive"))
      (node (ref "D229") (pin "2") (pinfunction "K_2") (pintype "passive"))
      (node (ref "D230") (pin "2") (pinfunction "K_2") (pintype "passive"))
      (node (ref "D231") (pin "2") (pinfunction "K_2") (pintype "passive"))
      (node (ref "D232") (pin "2") (pinfunction "K_2") (pintype "passive"))
      (node (ref "D233") (pin "2") (pinfunction "K_2") (pintype "passive"))
      (node (ref "D234") (pin "2") (pinfunction "K_2") (pintype "passive"))
      (node (ref "D235") (pin "2") (pinfunction "K_2") (pintype "passive"))
      (node (ref "D236") (pin "2") (pinfunction "K_2") (pintype "passive"))
      (node (ref "D237") (pin "2") (pinfunction "K_2") (pintype "passive"))
      (node (ref "D238") (pin "2") (pinfunction "K_2") (pintype "passive"))
      (node (ref "D239") (pin "2") (pinfunction "K_2") (pintype "passive"))
      (node (ref "D240") (pin "2") (pinfunction "K_2") (pintype "passive"))
      (node (ref "D259") (pin "2") (pinfunction "K_2") (pintype "passive"))
    )
    (net (code "19") (name "/row4") (class "Default")
      (node (ref "D242") (pin "2") (pinfunction "K_2") (pintype "passive"))
      (node (ref "D243") (pin "2") (pinfunction "K_2") (pintype "passive"))
      (node (ref "D244") (pin "2") (pinfunction "K_2") (pintype "passive"))
      (node (ref "D245") (pin "2") (pinfunction "K_2") (pintype "passive"))
      (node (ref "D246") (pin "2") (pinfunction "K_2") (pintype "passive"))
      (node (ref "D247") (pin "2") (pinfunction "K_2") (pintype "passive"))
      (node (ref "D248") (pin "2") (pinfunction "K_2") (pintype "passive"))
      (node (ref "D249") (pin "2") (pinfunction "K_2") (pintype "passive"))
      (node (ref "D250") (pin "2") (pinfunction "K_2") (pintype "passive"))
      (node (ref "D251") (pin "2") (pinfunction "K_2") (pintype "passive"))
      (node (ref "D252") (pin "2") (pinfunction "K_2") (pintype "passive"))
      (node (ref "D253") (pin "2") (pinfunction "K_2") (pintype "passive"))
      (node (ref "D254") (pin "2") (pinfunction "K_2") (pintype "passive"))
      (node (ref "D255") (pin "2") (pinfunction "K_2") (pintype "passive"))
    )
    (net (code "20") (name "/row5") (class "Default")
      (node (ref "D241") (pin "2") (pinfunction "K_2") (pintype "passive"))
      (node (ref "D256") (pin "2") (pinfunction "K_2") (pintype "passive"))
      (node (ref "D257") (pin "2") (pinfunction "K_2") (pintype "passive"))
      (node (ref "D258") (pin "2") (pinfunction "K_2") (pintype "passive"))
      (node (ref "D260") (pin "2") (pinfunction "K_2") (pintype "passive"))
      (node (ref "D261") (pin "2") (pinfunction "K_2") (pintype "passive"))
      (node (ref "D262") (pin "2") (pinfunction "K_2") (pintype "passive"))
      (node (ref "D263") (pin "2") (pinfunction "K_2") (pintype "passive"))
      (node (ref "D264") (pin "2") (pinfunction "K_2") (pintype "passive"))
      (node (ref "D265") (pin "2") (pinfunction "K_2") (pintype "passive"))
      (node (ref "D266") (pin "2") (pinfunction "K_2") (pintype "passive"))
    )
    (net (code "21") (name "Net-(D201-A)") (class "Default")
      (node (ref "D201") (pin "1") (pinfunction "A_1") (pintype "passive"))
      (node (ref "S201") (pin "1") (pinfunction "1_1") (pintype "passive"))
    )
    (net (code "22") (name "Net-(D202-A)") (class "Default")
      (node (ref "D202") (pin "1") (pinfunction "A_1") (pintype "passive"))
      (node (ref "S202") (pin "1") (pinfunction "1_1") (pintype "passive"))
    )
    (net (code "23") (name "Net-(D203-A)") (class "Default")
      (node (ref "D203") (pin "1") (pinfunction "A_1") (pintype "passive"))
      (node (ref "S203") (pin "1") (pinfunction "1_1") (pintype "passive"))
    )
    (net (code "24") (name "Net-(D204-A)") (class "Default")
      (node (ref "D204") (pin "1") (pinfunction "A_1") (pintype "passive"))
      (node (ref "S204") (pin "1") (pinfunction "1_1") (pintype "passive"))
    )
    (net (code "25") (name "Net-(D205-A)") (class "Default")
      (node (ref "D205") (pin "1") (pinfunction "A_1") (pintype "passive"))
      (node (ref "S205") (pin "1") (pinfunction "1_1") (pintype "passive"))
    )
    (net (code "26") (name "Net-(D206-A)") (class "Default")
      (node (ref "D206") (pin "1") (pinfunction "A_1") (pintype "passive"))
      (node (ref "S206") (pin "1") (pinfunction "1_1") (pintype "passive"))
    )
    (net (code "27") (name "Net-(D207-A)") (class "Default")
      (node (ref "D207") (pin "1") (pinfunction "A_1") (pintype "passive"))
      (node (ref "S207") (pin "1") (pinfunction "1_1") (pintype "passive"))
    )
    (net (code "28") (name "Net-(D208-A)") (class "Default")
      (node (ref "D208") (pin "1") (pinfunction "A_1") (pintype "passive"))
      (node (ref "S208") (pin "1") (pinfunction "1_1") (pintype "passive"))
    )
    (net (code "29") (name "Net-(D209-A)") (class "Default")
      (node (ref "D209") (pin "1") (pinfunction "A_1") (pintype "passive"))
      (node (ref "S209") (pin "1") (pinfunction "1_1") (pintype "passive"))
    )
    (net (code "30") (name "Net-(D210-A)") (class "Default")
      (node (ref "D210") (pin "1") (pinfunction "A_1") (pintype "passive"))
      (node (ref "S210") (pin "1") (pinfunction "1_1") (pintype "passive"))
    )
    (net (code "31") (name "Net-(D211-A)") (class "Default")
      (node (ref "D211") (pin "1") (pinfunction "A_1") (pintype "passive"))
      (node (ref "S211") (pin "1") (pinfunction "1_1") (pintype "passive"))
    )
    (net (code "32") (name "Net-(D212-A)") (class "Default")
      (node (ref "D212") (pin "1") (pinfunction "A_1") (pintype "passive"))
      (node (ref "S212") (pin "1") (pinfunction "1_1") (pintype "passive"))
    )
    (net (code "33") (name "Net-(D213-A)") (class "Default")
      (node (ref "D213") (pin "1") (pinfunction "A_1") (pintype "passive"))
      (node (ref "S213") (pin "1") (pinfunction "1_1") (pintype "passive"))
    )
    (net (code "34") (name "Net-(D214-A)") (class "Default")
      (node (ref "D214") (pin "1") (pinfunction "A_1") (pintype "passive"))
      (node (ref "S214") (pin "1") (pinfunction "1_1") (pintype "passive"))
    )
    (net (code "35") (name "Net-(D215-A)") (class "Default")
      (node (ref "D215") (pin "1") (pinfunction "A_1") (pintype "passive"))
      (node (ref "S215") (pin "1") (pinfunction "1_1") (pintype "passive"))
    )
    (net (code "36") (name "Net-(D216-A)") (class "Default")
      (node (ref "D216") (pin "1") (pinfunction "A_1") (pintype "passive"))
      (node (ref "S216") (pin "1") (pinfunction "1_1") (pintype "passive"))
    )
    (net (code "37") (name "Net-(D217-A)") (class "Default")
      (node (ref "D217") (pin "1") (pinfunction "A_1") (pintype "passive"))
      (node (ref "S217") (pin "1") (pinfunction "1_1") (pintype "passive"))
    )
    (net (code "38") (name "Net-(D218-A)") (class "Default")
      (node (ref "D218") (pin "1") (pinfunction "A_1") (pintype "passive"))
      (node (ref "S218") (pin "1") (pinfunction "1_1") (pintype "passive"))
    )
    (net (code "39") (name "Net-(D219-A)") (class "Default")
      (node (ref "D219") (pin "1") (pinfunction "A_1") (pintype "passive"))
      (node (ref "S219") (pin "1") (pinfunction "1_1") (pintype "passive"))
    )
    (net (code "40") (name "Net-(D220-A)") (class "Default")
      (node (ref "D220") (pin "1") (pinfunction "A_1") (pintype "passive"))
      (node (ref "S220") (pin "1") (pinfunction "1_1") (pintype "passive"))
    )
    (net (code "41") (name "Net-(D221-A)") (class "Default")
      (node (ref "D221") (pin "1") (pinfunction "A_1") (pintype "passive"))
      (node (ref "S221") (pin "1") (pinfunction "1_1") (pintype "passive"))
    )
    (net (code "42") (name "Net-(D222-A)") (class "Default")
      (node (ref "D222") (pin "1") (pinfunction "A_1") (pintype "passive"))
      (node (ref "S222") (pin "1") (pinfunction "1_1") (pintype "passive"))
    )
    (net (code "43") (name "Net-(D223-A)") (class "Default")
      (node (ref "D223") (pin "1") (pinfunction "A_1") (pintype "passive"))
      (node (ref "S223") (pin "1") (pinfunction "1_1") (pintype "passive"))
    )
    (net (code "44") (name "Net-(D224-A)") (class "Default")
      (node (ref "D224") (pin "1") (pinfunction "A_1") (pintype "passive"))
      (node (ref "S224") (pin "1") (pinfunction "1_1") (pintype "passive"))
    )
    (net (code "45") (name "Net-(D225-A)") (class "Default")
      (node (ref "D225") (pin "1") (pinfunction "A_1") (pintype "passive"))
      (node (ref "S225") (pin "1") (pinfunction "1_1") (pintype "passive"))
    )
    (net (code "46") (name "Net-(D226-A)") (class "Default")
      (node (ref "D226") (pin "1") (pinfunction "A_1") (pintype "passive"))
      (node (ref "S226") (pin "1") (pinfunction "1_1") (pintype "passive"))
    )
    (net (code "47") (name "Net-(D227-A)") (class "Default")
      (node (ref "D227") (pin "1") (pinfunction "A_1") (pintype "passive"))
      (node (ref "S227") (pin "1") (pinfunction "1_1") (pintype "passive"))
    )
    (net (code "48") (name "Net-(D228-A)") (class "Default")
      (node (ref "D228") (pin "1") (pinfunction "A_1") (pintype "passive"))
      (node (ref "S228") (pin "1") (pinfunction "1_1") (pintype "passive"))
    )
    (net (code "49") (name "Net-(D228_2-A)") (class "Default")
      (node (ref "D228_2") (pin "1") (pinfunction "A_1") (pintype "passive"))
      (node (ref "S228_2") (pin "1") (pinfunction "1_1") (pintype "passive"))
    )
    (net (code "50") (name "Net-(D229-A)") (class "Default")
      (node (ref "D229") (pin "1") (pinfunction "A_1") (pintype "passive"))
      (node (ref "S229") (pin "2") (pinfunction "2_2") (pintype "passive"))
    )
    (net (code "51") (name "Net-(D230-A)") (class "Default")
      (node (ref "D230") (pin "1") (pinfunction "A_1") (pintype "passive"))
      (node (ref "S230") (pin "1") (pinfunction "1_1") (pintype "passive"))
    )
    (net (code "52") (name "Net-(D231-A)") (class "Default")
      (node (ref "D231") (pin "1") (pinfunction "A_1") (pintype "passive"))
      (node (ref "S231") (pin "1") (pinfunction "1_1") (pintype "passive"))
    )
    (net (code "53") (name "Net-(D232-A)") (class "Default")
      (node (ref "D232") (pin "1") (pinfunction "A_1") (pintype "passive"))
      (node (ref "S232") (pin "1") (pinfunction "1_1") (pintype "passive"))
    )
    (net (code "54") (name "Net-(D233-A)") (class "Default")
      (node (ref "D233") (pin "1") (pinfunction "A_1") (pintype "passive"))
      (node (ref "S233") (pin "1") (pinfunction "1_1") (pintype "passive"))
    )
    (net (code "55") (name "Net-(D234-A)") (class "Default")
      (node (ref "D234") (pin "1") (pinfunction "A_1") (pintype "passive"))
      (node (ref "S234") (pin "1") (pinfunction "1_1") (pintype "passive"))
    )
    (net (code "56") (name "Net-(D235-A)") (class "Default")
      (node (ref "D235") (pin "1") (pinfunction "A_1") (pintype "passive"))
      (node (ref "S235") (pin "1") (pinfunction "1_1") (pintype "passive"))
    )
    (net (code "57") (name "Net-(D236-A)") (class "Default")
      (node (ref "D236") (pin "1") (pinfunction "A_1") (pintype "passive"))
      (node (ref "S236") (pin "1") (pinfunction "1_1") (pintype "passive"))
    )
    (net (code "58") (name "Net-(D237-A)") (class "Default")
      (node (ref "D237") (pin "1") (pinfunction "A_1") (pintype "passive"))
      (node (ref "S237") (pin "1") (pinfunction "1_1") (pintype "passive"))
    )
    (net (code "59") (name "Net-(D238-A)") (class "Default")
      (node (ref "D238") (pin "1") (pinfunction "A_1") (pintype "passive"))
      (node (ref "S238") (pin "1") (pinfunction "1_1") (pintype "passive"))
    )
    (net (code "60") (name "Net-(D239-A)") (class "Default")
      (node (ref "D239") (pin "1") (pinfunction "A_1") (pintype "passive"))
      (node (ref "S239") (pin "1") (pinfunction "1_1") (pintype "passive"))
    )
    (net (code "61") (name "Net-(D240-A)") (class "Default")
      (node (ref "D240") (pin "1") (pinfunction "A_1") (pintype "passive"))
      (node (ref "S240") (pin "1") (pinfunction "1_1") (pintype "passive"))
    )
    (net (code "62") (name "Net-(D241-A)") (class "Default")
      (node (ref "D241") (pin "1") (pinfunction "A_1") (pintype "passive"))
      (node (ref "S241") (pin "2") (pinfunction "2_2") (pintype "passive"))
    )
    (net (code "63") (name "Net-(D242-A)") (class "Default")
      (node (ref "D242") (pin "1") (pinfunction "A_1") (pintype "passive"))
      (node (ref "S242") (pin "1") (pinfunction "1_1") (pintype "passive"))
      (node (ref "S242_1") (pin "1") (pinfunction "1_1") (pintype "passive"))
    )
    (net (code "64") (name "Net-(D243-A)") (class "Default")
      (node (ref "D243") (pin "1") (pinfunction "A_1") (pintype "passive"))
      (node (ref "S243") (pin "1") (pinfunction "1_1") (pintype "passive"))
    )
    (net (code "65") (name "Net-(D244-A)") (class "Default")
      (node (ref "D244") (pin "1") (pinfunction "A_1") (pintype "passive"))
      (node (ref "S244") (pin "2") (pinfunction "2_2") (pintype "passive"))
    )
    (net (code "66") (name "Net-(D245-A)") (class "Default")
      (node (ref "D245") (pin "1") (pinfunction "A_1") (pintype "passive"))
      (node (ref "S245") (pin "1") (pinfunction "1_1") (pintype "passive"))
    )
    (net (code "67") (name "Net-(D246-A)") (class "Default")
      (node (ref "D246") (pin "1") (pinfunction "A_1") (pintype "passive"))
      (node (ref "S246") (pin "1") (pinfunction "1_1") (pintype "passive"))
    )
    (net (code "68") (name "Net-(D247-A)") (class "Default")
      (node (ref "D247") (pin "1") (pinfunction "A_1") (pintype "passive"))
      (node (ref "S247") (pin "1") (pinfunction "1_1") (pintype "passive"))
    )
    (net (code "69") (name "Net-(D248-A)") (class "Default")
      (node (ref "D248") (pin "1") (pinfunction "A_1") (pintype "passive"))
      (node (ref "S248") (pin "1") (pinfunction "1_1") (pintype "passive"))
    )
    (net (code "70") (name "Net-(D249-A)") (class "Default")
      (node (ref "D249") (pin "1") (pinfunction "A_1") (pintype "passive"))
      (node (ref "S249") (pin "1") (pinfunction "1_1") (pintype "passive"))
    )
    (net (code "71") (name "Net-(D250-A)") (class "Default")
      (node (ref "D250") (pin "1") (pinfunction "A_1") (pintype "passive"))
      (node (ref "S250") (pin "1") (pinfunction "1_1") (pintype "passive"))
    )
    (net (code "72") (name "Net-(D251-A)") (class "Default")
      (node (ref "D251") (pin "1") (pinfunction "A_1") (pintype "passive"))
      (node (ref "S251") (pin "1") (pinfunction "1_1") (pintype "passive"))
    )
    (net (code "73") (name "Net-(D252-A)") (class "Default")
      (node (ref "D252") (pin "1") (pinfunction "A_1") (pintype "passive"))
      (node (ref "S252") (pin "1") (pinfunction "1_1") (pintype "passive"))
    )
    (net (code "74") (name "Net-(D253-A)") (class "Default")
      (node (ref "D253") (pin "1") (pinfunction "A_1") (pintype "passive"))
      (node (ref "S253") (pin "1") (pinfunction "1_1") (pintype "passive"))
    )
    (net (code "75") (name "Net-(D254-A)") (class "Default")
      (node (ref "D254") (pin "1") (pinfunction "A_1") (pintype "passive"))
      (node (ref "S254") (pin "1") (pinfunction "1_1") (pintype "passive"))
    )
    (net (code "76") (name "Net-(D255-A)") (class "Default")
      (node (ref "D255") (pin "1") (pinfunction "A_1") (pintype "passive"))
      (node (ref "S256") (pin "1") (pinfunction "1_1") (pintype "passive"))
    )
    (net (code "77") (name "Net-(D256-A)") (class "Default")
      (node (ref "D256") (pin "1") (pinfunction "A_1") (pintype "passive"))
      (node (ref "S269") (pin "1") (pinfunction "1_1") (pintype "passive"))
    )
    (net (code "78") (name "Net-(D257-A)") (class "Default")
      (node (ref "D257") (pin "1") (pinfunction "A_1") (pintype "passive"))
      (node (ref "S257") (pin "2") (pinfunction "2_2") (pintype "passive"))
    )
    (net (code "79") (name "Net-(D258-A)") (class "Default")
      (node (ref "D258") (pin "1") (pinfunction "A_1") (pintype "passive"))
      (node (ref "S258") (pin "1") (pinfunction "1_1") (pintype "passive"))
    )
    (net (code "80") (name "Net-(D260-A)") (class "Default")
      (node (ref "D260") (pin "1") (pinfunction "A_1") (pintype "passive"))
      (node (ref "S260") (pin "1") (pinfunction "1_1") (pintype "passive"))
    )
    (net (code "81") (name "Net-(D261-A)") (class "Default")
      (node (ref "D261") (pin "1") (pinfunction "A_1") (pintype "passive"))
      (node (ref "S261") (pin "1") (pinfunction "1_1") (pintype "passive"))
      (node (ref "S261_1") (pin "1") (pinfunction "1_1") (pintype "passive"))
    )
    (net (code "82") (name "Net-(D262-A)") (class "Default")
      (node (ref "D262") (pin "1") (pinfunction "A_1") (pintype "passive"))
      (node (ref "S262") (pin "2") (pinfunction "2_2") (pintype "passive"))
      (node (ref "S262_1") (pin "2") (pinfunction "2_2") (pintype "passive"))
    )
    (net (code "83") (name "Net-(D263-A)") (class "Default")
      (node (ref "D263") (pin "1") (pinfunction "A_1") (pintype "passive"))
      (node (ref "S263") (pin "2") (pinfunction "2_2") (pintype "passive"))
      (node (ref "S263_1") (pin "2") (pinfunction "2_2") (pintype "passive"))
    )
    (net (code "84") (name "Net-(D264-A)") (class "Default")
      (node (ref "D264") (pin "1") (pinfunction "A_1") (pintype "passive"))
      (node (ref "S264") (pin "1") (pinfunction "1_1") (pintype "passive"))
      (node (ref "S264_1") (pin "2") (pinfunction "2_2") (pintype "passive"))
    )
    (net (code "85") (name "Net-(D265-A)") (class "Default")
      (node (ref "D265") (pin "1") (pinfunction "A_1") (pintype "passive"))
      (node (ref "S265") (pin "2") (pinfunction "2_2") (pintype "passive"))
      (node (ref "S265_1") (pin "1") (pinfunction "1_1") (pintype "passive"))
    )
    (net (code "86") (name "Net-(D266-A)") (class "Default")
      (node (ref "D266") (pin "1") (pinfunction "A_1") (pintype "passive"))
      (node (ref "S266") (pin "1") (pinfunction "1_1") (pintype "passive"))
    )
    (net (code "87") (name "unconnected-(STAB1-Pad1)") (class "Default")
      (node (ref "STAB1") (pin "1") (pinfunction "1_1") (pintype "passive"))
    )
    (net (code "88") (name "unconnected-(STAB2-Pad1)") (class "Default")
      (node (ref "STAB2") (pin "1") (pinfunction "1_1") (pintype "passive"))
    )
    (net (code "89") (name "unconnected-(STAB3-Pad1)") (class "Default")
      (node (ref "STAB3") (pin "1") (pinfunction "1_1") (pintype "passive"))
    )
  )
)
